# 04_-_OLD_Display_Pi_Zero_USB_Host.net
KiCad netlist of a schematic drawn in Altium Designer
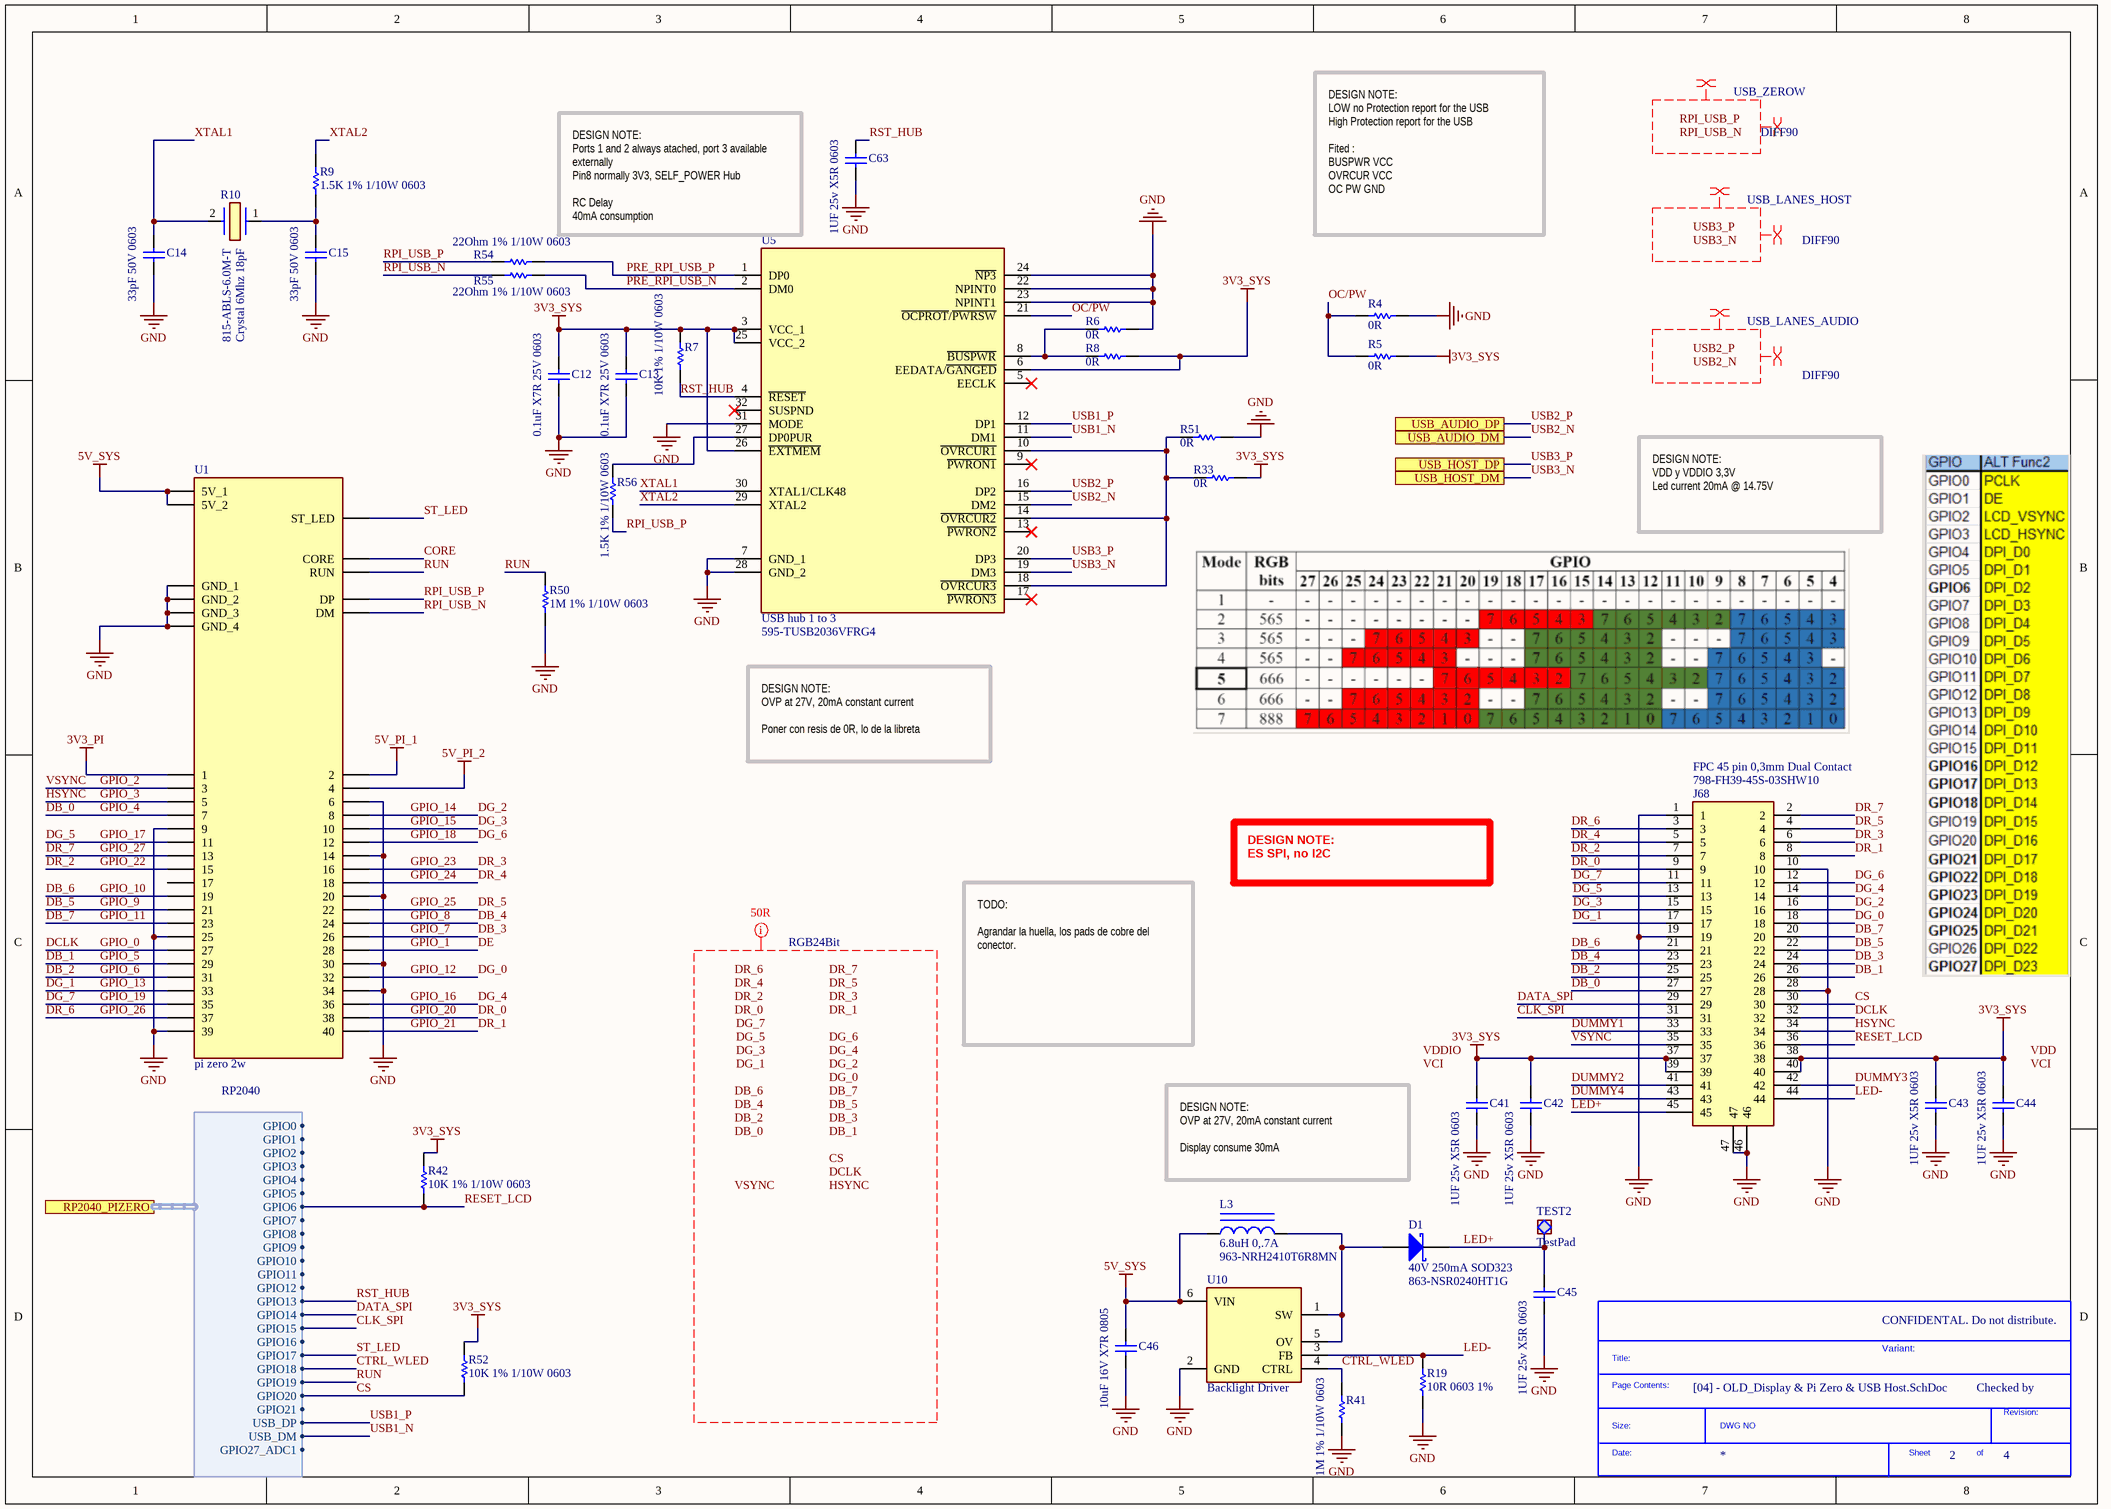
[diagram p0: [04] - OLD_Display & Pi Zero & USB Host.SchDoc]

(export (version "E")
  (design (tool "Eeschema 10.0.6"))
  (components
    (comp (ref "*") (value "SDTitleBlock") (libsource (lib "*") (part "SDTitleBlock")))
    (comp (ref "C12")
      (value "0.1uF X7R 25V 0603")
      (footprint "C 0603/1608")
      (fields
        (field (name "MANUFACTURER") "Wurth Electronics")
        (field (name "MANUFACTURER PART NUMBER") "885012206071")
        (field (name "TOLERANCE") "10%")
      )
      (libsource (lib "altium-import") (part "root_1_885012206071_"))
    )
    (comp (ref "C13")
      (value "0.1uF X7R 25V 0603")
      (footprint "C 0603/1608")
      (fields
        (field (name "MANUFACTURER") "Wurth Electronics")
        (field (name "MANUFACTURER PART NUMBER") "885012206071")
        (field (name "TOLERANCE") "10%")
      )
      (libsource (lib "altium-import") (part "root_1_885012206071_"))
    )
    (comp (ref "C14")
      (value "33pF 50V 0603")
      (footprint "C 0603/1608")
      (description "0603 33 pF 50 V ±5 % Tolerance NP0 SMT Multilayer Ceramic Capacitor")
      (fields
        (field (name "MANUFACTURER") "Yageo")
        (field (name "MANUFACTURER PART NUMBER") "CC0603JRNPO9BN330")
      )
      (libsource (lib "GBA") (part "CC0603JRNPO9BN330"))
    )
    (comp (ref "C15")
      (value "33pF 50V 0603")
      (footprint "C 0603/1608")
      (description "0603 33 pF 50 V ±5 % Tolerance NP0 SMT Multilayer Ceramic Capacitor")
      (fields
        (field (name "MANUFACTURER") "Yageo")
        (field (name "MANUFACTURER PART NUMBER") "CC0603JRNPO9BN330")
      )
      (libsource (lib "GBA") (part "CC0603JRNPO9BN330"))
    )
    (comp (ref "C41")
      (value "1UF 25v X5R 0603")
      (footprint "C 0603/1608")
      (description "CAP CER 1UF 25V X5R 0603")
      (fields
        (field (name "MANUFACTURER") "Yageo")
        (field (name "MANUFACTURER PART NUMBER") "CC0603KRX5R8BB105")
      )
      (libsource (lib "CM3Board_V1I2") (part "CC0603KRX5R8BB105"))
    )
    (comp (ref "C42")
      (value "1UF 25v X5R 0603")
      (footprint "C 0603/1608")
      (description "CAP CER 1UF 25V X5R 0603")
      (fields
        (field (name "MANUFACTURER") "Yageo")
        (field (name "MANUFACTURER PART NUMBER") "CC0603KRX5R8BB105")
      )
      (libsource (lib "CM3Board_V1I2") (part "CC0603KRX5R8BB105"))
    )
    (comp (ref "C43")
      (value "1UF 25v X5R 0603")
      (footprint "C 0603/1608")
      (description "CAP CER 1UF 25V X5R 0603")
      (fields
        (field (name "MANUFACTURER") "Yageo")
        (field (name "MANUFACTURER PART NUMBER") "CC0603KRX5R8BB105")
      )
      (libsource (lib "CM3Board_V1I2") (part "CC0603KRX5R8BB105"))
    )
    (comp (ref "C44")
      (value "1UF 25v X5R 0603")
      (footprint "C 0603/1608")
      (description "CAP CER 1UF 25V X5R 0603")
      (fields
        (field (name "MANUFACTURER") "Yageo")
        (field (name "MANUFACTURER PART NUMBER") "CC0603KRX5R8BB105")
      )
      (libsource (lib "CM3Board_V1I2") (part "CC0603KRX5R8BB105"))
    )
    (comp (ref "C45")
      (value "1UF 25v X5R 0603")
      (footprint "C 0603/1608")
      (description "CAP CER 1UF 25V X5R 0603")
      (fields
        (field (name "MANUFACTURER") "Yageo")
        (field (name "MANUFACTURER PART NUMBER") "CC0603KRX5R8BB105")
      )
      (libsource (lib "CM3Board_V1I2") (part "CC0603KRX5R8BB105"))
    )
    (comp (ref "C46")
      (value "10uF 16V X7R 0805")
      (footprint "C 0805/2012")
      (description "CAP CER 10UF 16V X7R 0805")
      (fields
        (field (name "MANUFACTURER") "Samsung Electro-Mechanics")
        (field (name "MANUFACTURER PART NUMBER") "CL21B106KOQNNNE")
      )
      (libsource (lib "CM3Board_V1I2") (part "CL21B106KOQNNNE"))
    )
    (comp (ref "C63")
      (value "1UF 25v X5R 0603")
      (footprint "C 0603/1608")
      (description "CAP CER 1UF 25V X5R 0603")
      (fields
        (field (name "MANUFACTURER") "Yageo")
        (field (name "MANUFACTURER PART NUMBER") "CC0603KRX5R8BB105")
      )
      (libsource (lib "CM3Board_V1I2") (part "CC0603KRX5R8BB105"))
    )
    (comp (ref "D1")
      (value "40V 250mA SOD323")
      (footprint "SOD-323")
      (description "DIODE SCHOTTKY 40V 250MA SOD323")
      (fields
        (field (name "MANUFACTURER") "ON Semiconductor")
        (field (name "MANUFACTURER PART NUMBER") "NSR0240HT1G")
        (field (name "SUPPLIER PART NUMBER 1") "863-NSR0240HT1G")
      )
      (libsource (lib "DPI_LVDS") (part "NSR0240HT1G"))
    )
    (comp (ref "J68")
      (value "FPC 45 pin 0,3mm Dual Contact")
      (footprint "FH3945S03SHW10")
      (description "FFC FPC Connectors Horizontal Mounting Angle Beige 0.3 mm - Pitch 45 Positions")
      (fields
        (field (name "MANUFACTURER") "Hirose")
        (field (name "MANUFACTURER PART NUMBER") "FH39-45S-0.3SHW(10)")
        (field (name "SUPPLIER PART NUMBER 1") "798-FH39-45S-03SHW10")
      )
      (libsource (lib "GBA") (part "FH39-45S-0.3SHW(10)"))
    )
    (comp (ref "L3")
      (value "6.8uH 0,.7A")
      (footprint "NRH2410T6R8MN")
      (description "Inductor Power Shielded Wirewound 6.8uH 20% 100KHz Ferrite 0.57A 0.492Ohm DCR T/R")
      (fields
        (field (name "MANUFACTURER") "Taiyo Yuden")
        (field (name "MANUFACTURER PART NUMBER") "NRH2410T6R8MN")
        (field (name "SUPPLIER PART NUMBER 1") "963-NRH2410T6R8MN")
      )
      (libsource (lib "GBA") (part "NRH2410T6R8MN"))
    )
    (comp (ref "R4")
      (value "0R")
      (footprint "R 0603/1608")
      (description "RES SMD 0 OHM JUMPER 1/10W 0603")
      (fields
        (field (name "MANUFACTURER") "Yageo")
        (field (name "MANUFACTURER PART NUMBER") "RC0603JR-070RL")
      )
      (libsource (lib "CM3Board_V1I2") (part "RC0603JR-070RL"))
    )
    (comp (ref "R5")
      (value "0R")
      (footprint "R 0603/1608")
      (description "RES SMD 0 OHM JUMPER 1/10W 0603")
      (fields
        (field (name "MANUFACTURER") "Yageo")
        (field (name "MANUFACTURER PART NUMBER") "RC0603JR-070RL")
      )
      (libsource (lib "CM3Board_V1I2") (part "RC0603JR-070RL"))
    )
    (comp (ref "R6")
      (value "0R")
      (footprint "R 0603/1608")
      (description "RES SMD 0 OHM JUMPER 1/10W 0603")
      (fields
        (field (name "MANUFACTURER") "Yageo")
        (field (name "MANUFACTURER PART NUMBER") "RC0603JR-070RL")
      )
      (libsource (lib "CM3Board_V1I2") (part "RC0603JR-070RL"))
    )
    (comp (ref "R7")
      (value "10K 1% 1/10W 0603")
      (footprint "R 0603/1608")
      (description "RES SMD 10K OHM 1% 1/10W 0603")
      (fields
        (field (name "MANUFACTURER") "Yageo")
        (field (name "MANUFACTURER PART NUMBER") "RC0603FR-0710KL")
      )
      (libsource (lib "GBA") (part "RC0603FR-0710KL"))
    )
    (comp (ref "R8")
      (value "0R")
      (footprint "R 0603/1608")
      (description "RES SMD 0 OHM JUMPER 1/10W 0603")
      (fields
        (field (name "MANUFACTURER") "Yageo")
        (field (name "MANUFACTURER PART NUMBER") "RC0603JR-070RL")
      )
      (libsource (lib "CM3Board_V1I2") (part "RC0603JR-070RL"))
    )
    (comp (ref "R9")
      (value "1.5K 1% 1/10W 0603")
      (footprint "R 0603/1608")
      (description "RES SMD 1.5K OHM 1% 1/10W 0603")
      (fields
        (field (name "MANUFACTURER") "Yageo")
        (field (name "MANUFACTURER PART NUMBER") "RC0603FR-071K5L")
      )
      (libsource (lib "CM3Board_V1I2") (part "RC0603FR-071K5L"))
    )
    (comp (ref "R10")
      (value "Crystal 6Mhz 18pF")
      (footprint "ABLS6000MHZB4T")
      (description "Crystal 6MHz ±30ppm (Tol) ±50ppm (Stability) 18pF FUND 100Ohm 2-Pin HC-49/US SMD T/R")
      (fields
        (field (name "MANUFACTURER") "Abracon")
        (field (name "MANUFACTURER PART NUMBER") "ABLS-6.000MHZ-B4-T")
        (field (name "SUPPLIER PART NUMBER 1") "815-ABLS-6.0M-T")
      )
      (libsource (lib "GBA") (part "ABLS-6.000MHZ-B4-T"))
    )
    (comp (ref "R19")
      (value "10R 0603 1%")
      (footprint "R 0603/1608")
      (description "High Precision-High Stability Chip Resistor Thin Film 0603 10Ohm 1% Paper T/R")
      (fields
        (field (name "MANUFACTURER") "Yageo")
        (field (name "MANUFACTURER PART NUMBER") "RT0603FRE0710RL")
      )
      (libsource (lib "GBA") (part "RT0603FRE0710RL"))
    )
    (comp (ref "R33")
      (value "0R")
      (footprint "R 0603/1608")
      (description "RES SMD 0 OHM JUMPER 1/10W 0603")
      (fields
        (field (name "MANUFACTURER") "Yageo")
        (field (name "MANUFACTURER PART NUMBER") "RC0603JR-070RL")
      )
      (libsource (lib "CM3Board_V1I2") (part "RC0603JR-070RL"))
    )
    (comp (ref "R41")
      (value "1M 1% 1/10W 0603")
      (footprint "R 0603/1608")
      (description "RES SMD 1M OHM 1% 1/10W 0603")
      (fields (field (name "TOLERANCE") "1%"))
      (libsource (lib "CM3Board_V1I2") (part "RC0603FR-071ML"))
    )
    (comp (ref "R42")
      (value "10K 1% 1/10W 0603")
      (footprint "R 0603/1608")
      (description "RES SMD 10K OHM 1% 1/10W 0603")
      (fields
        (field (name "MANUFACTURER") "Yageo")
        (field (name "MANUFACTURER PART NUMBER") "RC0603FR-0710KL")
      )
      (libsource (lib "GBA") (part "RC0603FR-0710KL"))
    )
    (comp (ref "R50")
      (value "1M 1% 1/10W 0603")
      (footprint "R 0603/1608")
      (description "RES SMD 1M OHM 1% 1/10W 0603")
      (fields (field (name "TOLERANCE") "1%"))
      (libsource (lib "CM3Board_V1I2") (part "RC0603FR-071ML"))
    )
    (comp (ref "R51")
      (value "0R")
      (footprint "R 0603/1608")
      (description "RES SMD 0 OHM JUMPER 1/10W 0603")
      (fields
        (field (name "MANUFACTURER") "Yageo")
        (field (name "MANUFACTURER PART NUMBER") "RC0603JR-070RL")
      )
      (libsource (lib "CM3Board_V1I2") (part "RC0603JR-070RL"))
    )
    (comp (ref "R52")
      (value "10K 1% 1/10W 0603")
      (footprint "R 0603/1608")
      (description "RES SMD 10K OHM 1% 1/10W 0603")
      (fields
        (field (name "MANUFACTURER") "Yageo")
        (field (name "MANUFACTURER PART NUMBER") "RC0603FR-0710KL")
      )
      (libsource (lib "GBA") (part "RC0603FR-0710KL"))
    )
    (comp (ref "R54")
      (value "22Ohm 1% 1/10W 0603")
      (footprint "R 0603/1608")
      (description "RES SMD 22 OHM 1% 1/10W 0603")
      (fields
        (field (name "MANUFACTURER") "Yageo")
        (field (name "MANUFACTURER PART NUMBER") "RC0603FR-0722RL")
      )
      (libsource (lib "CM3Board_V1I2") (part "RC0603FR-0722RL"))
    )
    (comp (ref "R55")
      (value "22Ohm 1% 1/10W 0603")
      (footprint "R 0603/1608")
      (description "RES SMD 22 OHM 1% 1/10W 0603")
      (fields
        (field (name "MANUFACTURER") "Yageo")
        (field (name "MANUFACTURER PART NUMBER") "RC0603FR-0722RL")
      )
      (libsource (lib "CM3Board_V1I2") (part "RC0603FR-0722RL"))
    )
    (comp (ref "R56")
      (value "1.5K 1% 1/10W 0603")
      (footprint "R 0603/1608")
      (description "RES SMD 1.5K OHM 1% 1/10W 0603")
      (fields
        (field (name "MANUFACTURER") "Yageo")
        (field (name "MANUFACTURER PART NUMBER") "RC0603FR-071K5L")
      )
      (libsource (lib "CM3Board_V1I2") (part "RC0603FR-071K5L"))
    )
    (comp (ref "TEST2")
      (value "TestPad")
      (footprint "TestPad")
      (description "Probe Pad, SMT, ROUND, 2.0MM")
      (libsource (lib "CM3Board") (part "PP_SMT_ROUND_2MM"))
    )
    (comp (ref "U1")
      (value "pi zero 2w")
      (footprint "Pi 2 Zero W")
      (description "Comprar los pogo 575-906015  x 60 y los de los tornillos x4 710-9774025151R")
      (libsource (lib "GBA") (part "PI ZERO 2W"))
    )
    (comp (ref "U5")
      (value "USB hub 1 to 3")
      (footprint "QFP80P900X900X160-32N")
      (description "2/3-port 12-Mbps USB full-speed hub with optional serial EEPROM interface 32-LQFP 0 to 70")
      (fields
        (field (name "MANUFACTURER") "Texas Instruments")
        (field (name "MANUFACTURER PART NUMBER") "TUSB2036VFRG4")
        (field (name "SUPPLIER PART NUMBER 1") "595-TUSB2036VFRG4")
      )
      (libsource (lib "GBA") (part "TUSB2036VFRG4"))
    )
    (comp (ref "U10")
      (value "Backlight Driver")
      (footprint "SOT95P280X145-6N")
      (description "AP3032 Series 9 V 1.3 MHz Surface Mount White LED Step-Up Converter - SOT-23-6")
      (fields (field (name "MANUFACTURER") "Diodes") (field (name "MANUFACTURER PART NUMBER") "AP3032KTR-G1"))
      (libsource (lib "GBA") (part "AP3032KTR-G1"))
    )
  )
  (nets
    (net (code "2") (name "/CLK_SPI") (class "Default")
      (node (ref "J68") (pin "31") (pinfunction "31_31") (pintype "passive"))
    )
    (net (code "3") (name "/CORE") (class "Default")
      (node (ref "U1") (pin "CORE") (pinfunction "CORE_CORE") (pintype "passive"))
    )
    (net (code "4") (name "/CS") (class "Default")
      (node (ref "J68") (pin "30") (pinfunction "30_30") (pintype "passive"))
      (node (ref "R52") (pin "1") (pinfunction "1_1") (pintype "passive"))
    )
    (net (code "5") (name "/CTRL_WLED") (class "Default")
      (node (ref "R41") (pin "2") (pinfunction "2_2") (pintype "passive"))
      (node (ref "U10") (pin "4") (pinfunction "CTRL_4") (pintype "passive"))
    )
    (net (code "6") (name "/DATA_SPI") (class "Default")
      (node (ref "J68") (pin "29") (pinfunction "29_29") (pintype "passive"))
    )
    (net (code "7") (name "/DB_0") (class "Default")
      (node (ref "J68") (pin "27") (pinfunction "27_27") (pintype "passive"))
      (node (ref "U1") (pin "7") (pinfunction "7_7") (pintype "passive"))
    )
    (net (code "8") (name "/DB_1") (class "Default")
      (node (ref "J68") (pin "26") (pinfunction "26_26") (pintype "passive"))
      (node (ref "U1") (pin "29") (pinfunction "29_29") (pintype "passive"))
    )
    (net (code "9") (name "/DB_2") (class "Default")
      (node (ref "J68") (pin "25") (pinfunction "25_25") (pintype "passive"))
      (node (ref "U1") (pin "31") (pinfunction "31_31") (pintype "passive"))
    )
    (net (code "10") (name "/DB_3") (class "Default")
      (node (ref "J68") (pin "24") (pinfunction "24_24") (pintype "passive"))
      (node (ref "U1") (pin "26") (pinfunction "26_26") (pintype "passive"))
    )
    (net (code "11") (name "/DB_4") (class "Default")
      (node (ref "J68") (pin "23") (pinfunction "23_23") (pintype "passive"))
      (node (ref "U1") (pin "24") (pinfunction "24_24") (pintype "passive"))
    )
    (net (code "12") (name "/DB_5") (class "Default")
      (node (ref "J68") (pin "22") (pinfunction "22_22") (pintype "passive"))
      (node (ref "U1") (pin "21") (pinfunction "21_21") (pintype "passive"))
    )
    (net (code "13") (name "/DB_6") (class "Default")
      (node (ref "J68") (pin "21") (pinfunction "21_21") (pintype "passive"))
      (node (ref "U1") (pin "19") (pinfunction "19_19") (pintype "passive"))
    )
    (net (code "14") (name "/DB_7") (class "Default")
      (node (ref "J68") (pin "20") (pinfunction "20_20") (pintype "passive"))
      (node (ref "U1") (pin "23") (pinfunction "23_23") (pintype "passive"))
    )
    (net (code "15") (name "/DCLK") (class "Default")
      (node (ref "J68") (pin "32") (pinfunction "32_32") (pintype "passive"))
      (node (ref "U1") (pin "27") (pinfunction "27_27") (pintype "passive"))
    )
    (net (code "16") (name "/DE") (class "Default")
      (node (ref "U1") (pin "28") (pinfunction "28_28") (pintype "passive"))
    )
    (net (code "17") (name "/DG_0") (class "Default")
      (node (ref "J68") (pin "18") (pinfunction "18_18") (pintype "passive"))
      (node (ref "U1") (pin "32") (pinfunction "32_32") (pintype "passive"))
    )
    (net (code "18") (name "/DG_1") (class "Default")
      (node (ref "J68") (pin "17") (pinfunction "17_17") (pintype "passive"))
      (node (ref "U1") (pin "33") (pinfunction "33_33") (pintype "passive"))
    )
    (net (code "19") (name "/DG_2") (class "Default")
      (node (ref "J68") (pin "16") (pinfunction "16_16") (pintype "passive"))
      (node (ref "U1") (pin "8") (pinfunction "8_8") (pintype "passive"))
    )
    (net (code "20") (name "/DG_3") (class "Default")
      (node (ref "J68") (pin "15") (pinfunction "15_15") (pintype "passive"))
      (node (ref "U1") (pin "10") (pinfunction "10_10") (pintype "passive"))
    )
    (net (code "21") (name "/DG_4") (class "Default")
      (node (ref "J68") (pin "14") (pinfunction "14_14") (pintype "passive"))
      (node (ref "U1") (pin "36") (pinfunction "36_36") (pintype "passive"))
    )
    (net (code "22") (name "/DG_5") (class "Default")
      (node (ref "J68") (pin "13") (pinfunction "13_13") (pintype "passive"))
      (node (ref "U1") (pin "11") (pinfunction "11_11") (pintype "passive"))
    )
    (net (code "23") (name "/DG_6") (class "Default")
      (node (ref "J68") (pin "12") (pinfunction "12_12") (pintype "passive"))
      (node (ref "U1") (pin "12") (pinfunction "12_12") (pintype "passive"))
    )
    (net (code "24") (name "/DG_7") (class "Default")
      (node (ref "J68") (pin "11") (pinfunction "11_11") (pintype "passive"))
      (node (ref "U1") (pin "35") (pinfunction "35_35") (pintype "passive"))
    )
    (net (code "25") (name "/DR_0") (class "Default")
      (node (ref "J68") (pin "9") (pinfunction "9_9") (pintype "passive"))
      (node (ref "U1") (pin "38") (pinfunction "38_38") (pintype "passive"))
    )
    (net (code "26") (name "/DR_1") (class "Default")
      (node (ref "J68") (pin "8") (pinfunction "8_8") (pintype "passive"))
      (node (ref "U1") (pin "40") (pinfunction "40_40") (pintype "passive"))
    )
    (net (code "27") (name "/DR_2") (class "Default")
      (node (ref "J68") (pin "7") (pinfunction "7_7") (pintype "passive"))
      (node (ref "U1") (pin "15") (pinfunction "15_15") (pintype "passive"))
    )
    (net (code "28") (name "/DR_3") (class "Default")
      (node (ref "J68") (pin "6") (pinfunction "6_6") (pintype "passive"))
      (node (ref "U1") (pin "16") (pinfunction "16_16") (pintype "passive"))
    )
    (net (code "29") (name "/DR_4") (class "Default")
      (node (ref "J68") (pin "5") (pinfunction "5_5") (pintype "passive"))
      (node (ref "U1") (pin "18") (pinfunction "18_18") (pintype "passive"))
    )
    (net (code "30") (name "/DR_5") (class "Default")
      (node (ref "J68") (pin "4") (pinfunction "4_4") (pintype "passive"))
      (node (ref "U1") (pin "22") (pinfunction "22_22") (pintype "passive"))
    )
    (net (code "31") (name "/DR_6") (class "Default")
      (node (ref "J68") (pin "3") (pinfunction "3_3") (pintype "passive"))
      (node (ref "U1") (pin "37") (pinfunction "37_37") (pintype "passive"))
    )
    (net (code "32") (name "/DR_7") (class "Default")
      (node (ref "J68") (pin "2") (pinfunction "2_2") (pintype "passive"))
      (node (ref "U1") (pin "13") (pinfunction "13_13") (pintype "passive"))
    )
    (net (code "33") (name "/DUMMY1") (class "Default")
      (node (ref "J68") (pin "33") (pinfunction "33_33") (pintype "passive"))
    )
    (net (code "34") (name "/DUMMY2") (class "Default")
      (node (ref "J68") (pin "41") (pinfunction "41_41") (pintype "passive"))
    )
    (net (code "35") (name "/DUMMY3") (class "Default")
      (node (ref "J68") (pin "42") (pinfunction "42_42") (pintype "passive"))
    )
    (net (code "36") (name "/DUMMY4") (class "Default")
      (node (ref "J68") (pin "43") (pinfunction "43_43") (pintype "passive"))
    )
    (net (code "37") (name "/GPIO_2") (class "Default")
      (node (ref "J68") (pin "35") (pinfunction "35_35") (pintype "passive"))
      (node (ref "U1") (pin "3") (pinfunction "3_3") (pintype "passive"))
    )
    (net (code "38") (name "/GPIO_3") (class "Default")
      (node (ref "J68") (pin "34") (pinfunction "34_34") (pintype "passive"))
      (node (ref "U1") (pin "5") (pinfunction "5_5") (pintype "passive"))
    )
    (net (code "39") (name "/LED+") (class "Default")
      (node (ref "C45") (pin "1") (pinfunction "1_1") (pintype "passive"))
      (node (ref "D1") (pin "1") (pinfunction "K_1") (pintype "passive"))
      (node (ref "J68") (pin "45") (pinfunction "45_45") (pintype "passive"))
      (node (ref "TEST2") (pin "1") (pinfunction "1_1") (pintype "passive"))
    )
    (net (code "40") (name "/LED-") (class "Default")
      (node (ref "J68") (pin "44") (pinfunction "44_44") (pintype "passive"))
      (node (ref "R19") (pin "2") (pinfunction "2_2") (pintype "passive"))
      (node (ref "U10") (pin "3") (pinfunction "FB_3") (pintype "passive"))
    )
    (net (code "41") (name "/OC{slash}PW") (class "Default")
      (node (ref "R4") (pin "1") (pinfunction "1_1") (pintype "passive"))
      (node (ref "R5") (pin "1") (pinfunction "1_1") (pintype "passive"))
      (node (ref "U5") (pin "21") (pinfunction "~{OCPROT}/~{PWRSW}_21") (pintype "passive"))
    )
    (net (code "42") (name "/PRE_RPI_USB_N") (class "Default")
      (node (ref "R55") (pin "2") (pinfunction "2_2") (pintype "passive"))
      (node (ref "U5") (pin "2") (pinfunction "DM0_2") (pintype "passive"))
    )
    (net (code "43") (name "/PRE_RPI_USB_P") (class "Default")
      (node (ref "R54") (pin "2") (pinfunction "2_2") (pintype "passive"))
      (node (ref "U5") (pin "1") (pinfunction "DP0_1") (pintype "passive"))
    )
    (net (code "44") (name "/RESET_LCD") (class "Default")
      (node (ref "J68") (pin "36") (pinfunction "36_36") (pintype "passive"))
      (node (ref "R42") (pin "1") (pinfunction "1_1") (pintype "passive"))
    )
    (net (code "45") (name "/RPI_USB_N") (class "Default")
      (node (ref "R55") (pin "1") (pinfunction "1_1") (pintype "passive"))
      (node (ref "U1") (pin "DM") (pinfunction "DM_DM") (pintype "passive"))
    )
    (net (code "46") (name "/RPI_USB_P") (class "Default")
      (node (ref "R54") (pin "1") (pinfunction "1_1") (pintype "passive"))
      (node (ref "R56") (pin "2") (pinfunction "2_2") (pintype "passive"))
      (node (ref "U1") (pin "DP") (pinfunction "DP_DP") (pintype "passive"))
    )
    (net (code "47") (name "/RST_HUB") (class "Default")
      (node (ref "C63") (pin "1") (pinfunction "1_1") (pintype "passive"))
      (node (ref "R7") (pin "1") (pinfunction "1_1") (pintype "passive"))
      (node (ref "U5") (pin "4") (pinfunction "~{RESET}_4") (pintype "passive"))
    )
    (net (code "48") (name "/RUN") (class "Default")
      (node (ref "R50") (pin "2") (pinfunction "2_2") (pintype "passive"))
      (node (ref "U1") (pin "RUN") (pinfunction "RUN_RUN") (pintype "passive"))
    )
    (net (code "49") (name "/ST_LED") (class "Default")
      (node (ref "U1") (pin "ST_LED") (pinfunction "ST_LED_ST_LED") (pintype "passive"))
    )
    (net (code "50") (name "/USB1_N") (class "Default")
      (node (ref "U5") (pin "11") (pinfunction "DM1_11") (pintype "passive"))
    )
    (net (code "51") (name "/USB1_P") (class "Default")
      (node (ref "U5") (pin "12") (pinfunction "DP1_12") (pintype "passive"))
    )
    (net (code "52") (name "/USB2_N") (class "Default")
      (node (ref "U5") (pin "15") (pinfunction "DM2_15") (pintype "passive"))
    )
    (net (code "53") (name "/USB2_P") (class "Default")
      (node (ref "U5") (pin "16") (pinfunction "DP2_16") (pintype "passive"))
    )
    (net (code "54") (name "/USB3_N") (class "Default")
      (node (ref "U5") (pin "19") (pinfunction "DM3_19") (pintype "passive"))
    )
    (net (code "55") (name "/USB3_P") (class "Default")
      (node (ref "U5") (pin "20") (pinfunction "DP3_20") (pintype "passive"))
    )
    (net (code "59") (name "/XTAL1") (class "Default")
      (node (ref "C14") (pin "2") (pinfunction "2_2") (pintype "passive"))
      (node (ref "R10") (pin "2") (pinfunction "CRYSTAL_2_2") (pintype "passive"))
      (node (ref "U5") (pin "30") (pinfunction "XTAL1/CLK48_30") (pintype "passive"))
    )
    (net (code "60") (name "/XTAL2") (class "Default")
      (node (ref "R9") (pin "2") (pinfunction "2_2") (pintype "passive"))
      (node (ref "U5") (pin "29") (pinfunction "XTAL2_29") (pintype "passive"))
    )
    (net (code "62") (name "3V3_PI") (class "Default")
      (node (ref "U1") (pin "1") (pinfunction "1_1") (pintype "passive"))
    )
    (net (code "63") (name "3V3_SYS") (class "Default")
      (node (ref "C12") (pin "1") (pinfunction "1_1") (pintype "passive"))
      (node (ref "C13") (pin "1") (pinfunction "1_1") (pintype "passive"))
      (node (ref "C41") (pin "1") (pinfunction "1_1") (pintype "passive"))
      (node (ref "C42") (pin "1") (pinfunction "1_1") (pintype "passive"))
      (node (ref "C43") (pin "1") (pinfunction "1_1") (pintype "passive"))
      (node (ref "C44") (pin "1") (pinfunction "1_1") (pintype "passive"))
      (node (ref "J68") (pin "37") (pinfunction "37_37") (pintype "passive"))
      (node (ref "J68") (pin "38") (pinfunction "38_38") (pintype "passive"))
      (node (ref "J68") (pin "39") (pinfunction "39_39") (pintype "passive"))
      (node (ref "J68") (pin "40") (pinfunction "40_40") (pintype "passive"))
      (node (ref "R33") (pin "1") (pinfunction "1_1") (pintype "passive"))
      (node (ref "R42") (pin "2") (pinfunction "2_2") (pintype "passive"))
      (node (ref "R5") (pin "2") (pinfunction "2_2") (pintype "passive"))
      (node (ref "R52") (pin "2") (pinfunction "2_2") (pintype "passive"))
      (node (ref "R7") (pin "2") (pinfunction "2_2") (pintype "passive"))
      (node (ref "R8") (pin "1") (pinfunction "1_1") (pintype "passive"))
      (node (ref "U5") (pin "25") (pinfunction "VCC_2_25") (pintype "passive"))
      (node (ref "U5") (pin "26") (pinfunction "~{EXTMEM}_26") (pintype "passive"))
      (node (ref "U5") (pin "3") (pinfunction "VCC_1_3") (pintype "passive"))
      (node (ref "U5") (pin "6") (pinfunction "EEDATA/~{GANGED}_6") (pintype "passive"))
    )
    (net (code "64") (name "5V_PI_1") (class "Default")
      (node (ref "U1") (pin "2") (pinfunction "2_2") (pintype "passive"))
    )
    (net (code "65") (name "5V_PI_2") (class "Default")
      (node (ref "U1") (pin "4") (pinfunction "4_4") (pintype "passive"))
    )
    (net (code "66") (name "5V_SYS") (class "Default")
      (node (ref "C46") (pin "2") (pinfunction "2_2") (pintype "passive"))
      (node (ref "L3") (pin "1") (pinfunction "1_1") (pintype "passive"))
      (node (ref "U1") (pin "5V_1") (pinfunction "5V_1_5V_1") (pintype "passive"))
      (node (ref "U1") (pin "5V_2") (pinfunction "5V_2_5V_2") (pintype "passive"))
      (node (ref "U10") (pin "6") (pinfunction "VIN_6") (pintype "passive"))
    )
    (net (code "67") (name "GND") (class "Default")
      (node (ref "C12") (pin "2") (pinfunction "2_2") (pintype "passive"))
      (node (ref "C13") (pin "2") (pinfunction "2_2") (pintype "passive"))
      (node (ref "C14") (pin "1") (pinfunction "1_1") (pintype "passive"))
      (node (ref "C15") (pin "2") (pinfunction "2_2") (pintype "passive"))
      (node (ref "C41") (pin "2") (pinfunction "2_2") (pintype "passive"))
      (node (ref "C42") (pin "2") (pinfunction "2_2") (pintype "passive"))
      (node (ref "C43") (pin "2") (pinfunction "2_2") (pintype "passive"))
      (node (ref "C44") (pin "2") (pinfunction "2_2") (pintype "passive"))
      (node (ref "C45") (pin "2") (pinfunction "2_2") (pintype "passive"))
      (node (ref "C46") (pin "1") (pinfunction "1_1") (pintype "passive"))
      (node (ref "C63") (pin "2") (pinfunction "2_2") (pintype "passive"))
      (node (ref "J68") (pin "1") (pinfunction "1_1") (pintype "passive"))
      (node (ref "J68") (pin "10") (pinfunction "10_10") (pintype "passive"))
      (node (ref "J68") (pin "19") (pinfunction "19_19") (pintype "passive"))
      (node (ref "J68") (pin "28") (pinfunction "28_28") (pintype "passive"))
      (node (ref "J68") (pin "46") (pinfunction "46_46") (pintype "passive"))
      (node (ref "J68") (pin "47") (pinfunction "47_47") (pintype "passive"))
      (node (ref "R19") (pin "1") (pinfunction "1_1") (pintype "passive"))
      (node (ref "R4") (pin "2") (pinfunction "2_2") (pintype "passive"))
      (node (ref "R41") (pin "1") (pinfunction "1_1") (pintype "passive"))
      (node (ref "R50") (pin "1") (pinfunction "1_1") (pintype "passive"))
      (node (ref "R51") (pin "1") (pinfunction "1_1") (pintype "passive"))
      (node (ref "R6") (pin "2") (pinfunction "2_2") (pintype "passive"))
      (node (ref "U1") (pin "14") (pinfunction "14_14") (pintype "passive"))
      (node (ref "U1") (pin "20") (pinfunction "20_20") (pintype "passive"))
      (node (ref "U1") (pin "25") (pinfunction "25_25") (pintype "passive"))
      (node (ref "U1") (pin "30") (pinfunction "30_30") (pintype "passive"))
      (node (ref "U1") (pin "34") (pinfunction "34_34") (pintype "passive"))
      (node (ref "U1") (pin "39") (pinfunction "39_39") (pintype "passive"))
      (node (ref "U1") (pin "6") (pinfunction "6_6") (pintype "passive"))
      (node (ref "U1") (pin "9") (pinfunction "9_9") (pintype "passive"))
      (node (ref "U1") (pin "GND_1") (pinfunction "GND_1_GND_1") (pintype "passive"))
      (node (ref "U1") (pin "GND_2") (pinfunction "GND_2_GND_2") (pintype "passive"))
      (node (ref "U1") (pin "GND_3") (pinfunction "GND_3_GND_3") (pintype "passive"))
      (node (ref "U1") (pin "GND_4") (pinfunction "GND_4_GND_4") (pintype "passive"))
      (node (ref "U10") (pin "2") (pinfunction "GND_2") (pintype "passive"))
      (node (ref "U5") (pin "22") (pinfunction "NPINT0_22") (pintype "passive"))
      (node (ref "U5") (pin "23") (pinfunction "NPINT1_23") (pintype "passive"))
      (node (ref "U5") (pin "24") (pinfunction "~{NP3}_24") (pintype "passive"))
      (node (ref "U5") (pin "28") (pinfunction "GND_2_28") (pintype "passive"))
      (node (ref "U5") (pin "31") (pinfunction "MODE_31") (pintype "passive"))
      (node (ref "U5") (pin "7") (pinfunction "GND_1_7") (pintype "passive"))
    )
    (net (code "68") (name "Net-(C15-Pad1)") (class "Default")
      (node (ref "C15") (pin "1") (pinfunction "1_1") (pintype "passive"))
      (node (ref "R10") (pin "1") (pinfunction "1_1") (pintype "passive"))
      (node (ref "R9") (pin "1") (pinfunction "1_1") (pintype "passive"))
    )
    (net (code "69") (name "Net-(D1-A)") (class "Default")
      (node (ref "D1") (pin "2") (pinfunction "A_2") (pintype "passive"))
      (node (ref "L3") (pin "2") (pinfunction "2_2") (pintype "passive"))
      (node (ref "U10") (pin "1") (pinfunction "SW_1") (pintype "passive"))
      (node (ref "U10") (pin "5") (pinfunction "OV_5") (pintype "passive"))
    )
    (net (code "70") (name "Net-(U5-DP0PUR)") (class "Default")
      (node (ref "R56") (pin "1") (pinfunction "1_1") (pintype "passive"))
      (node (ref "U5") (pin "27") (pinfunction "DP0PUR_27") (pintype "passive"))
    )
    (net (code "71") (name "Net-(U5-~{BUSPWR})") (class "Default")
      (node (ref "R6") (pin "1") (pinfunction "1_1") (pintype "passive"))
      (node (ref "R8") (pin "2") (pinfunction "2_2") (pintype "passive"))
      (node (ref "U5") (pin "8") (pinfunction "~{BUSPWR}_8") (pintype "passive"))
    )
    (net (code "72") (name "Net-(U5-~{OVRCUR1})") (class "Default")
      (node (ref "R33") (pin "2") (pinfunction "2_2") (pintype "passive"))
      (node (ref "R51") (pin "2") (pinfunction "2_2") (pintype "passive"))
      (node (ref "U5") (pin "10") (pinfunction "~{OVRCUR1}_10") (pintype "passive"))
      (node (ref "U5") (pin "14") (pinfunction "~{OVRCUR2}_14") (pintype "passive"))
      (node (ref "U5") (pin "18") (pinfunction "~{OVRCUR3}_18") (pintype "passive"))
    )
    (net (code "73") (name "unconnected-(U1-Pad17)") (class "Default")
      (node (ref "U1") (pin "17") (pinfunction "17_17") (pintype "passive"))
    )
    (net (code "74") (name "unconnected-(U5-EECLK-Pad5)") (class "Default")
      (node (ref "U5") (pin "5") (pinfunction "EECLK_5") (pintype "passive+no_connect"))
    )
    (net (code "75") (name "unconnected-(U5-SUSPND-Pad32)") (class "Default")
      (node (ref "U5") (pin "32") (pinfunction "SUSPND_32") (pintype "passive+no_connect"))
    )
    (net (code "76") (name "unconnected-(U5-~{PWRON1}-Pad9)") (class "Default")
      (node (ref "U5") (pin "9") (pinfunction "~{PWRON1}_9") (pintype "passive+no_connect"))
    )
    (net (code "77") (name "unconnected-(U5-~{PWRON2}-Pad13)") (class "Default")
      (node (ref "U5") (pin "13") (pinfunction "~{PWRON2}_13") (pintype "passive+no_connect"))
    )
    (net (code "78") (name "unconnected-(U5-~{PWRON3}-Pad17)") (class "Default")
      (node (ref "U5") (pin "17") (pinfunction "~{PWRON3}_17") (pintype "passive+no_connect"))
    )
  )
)
